# LAB03-1_2020-11-16_17-36-06.net
KiCad netlist of a schematic drawn in EasyEDA
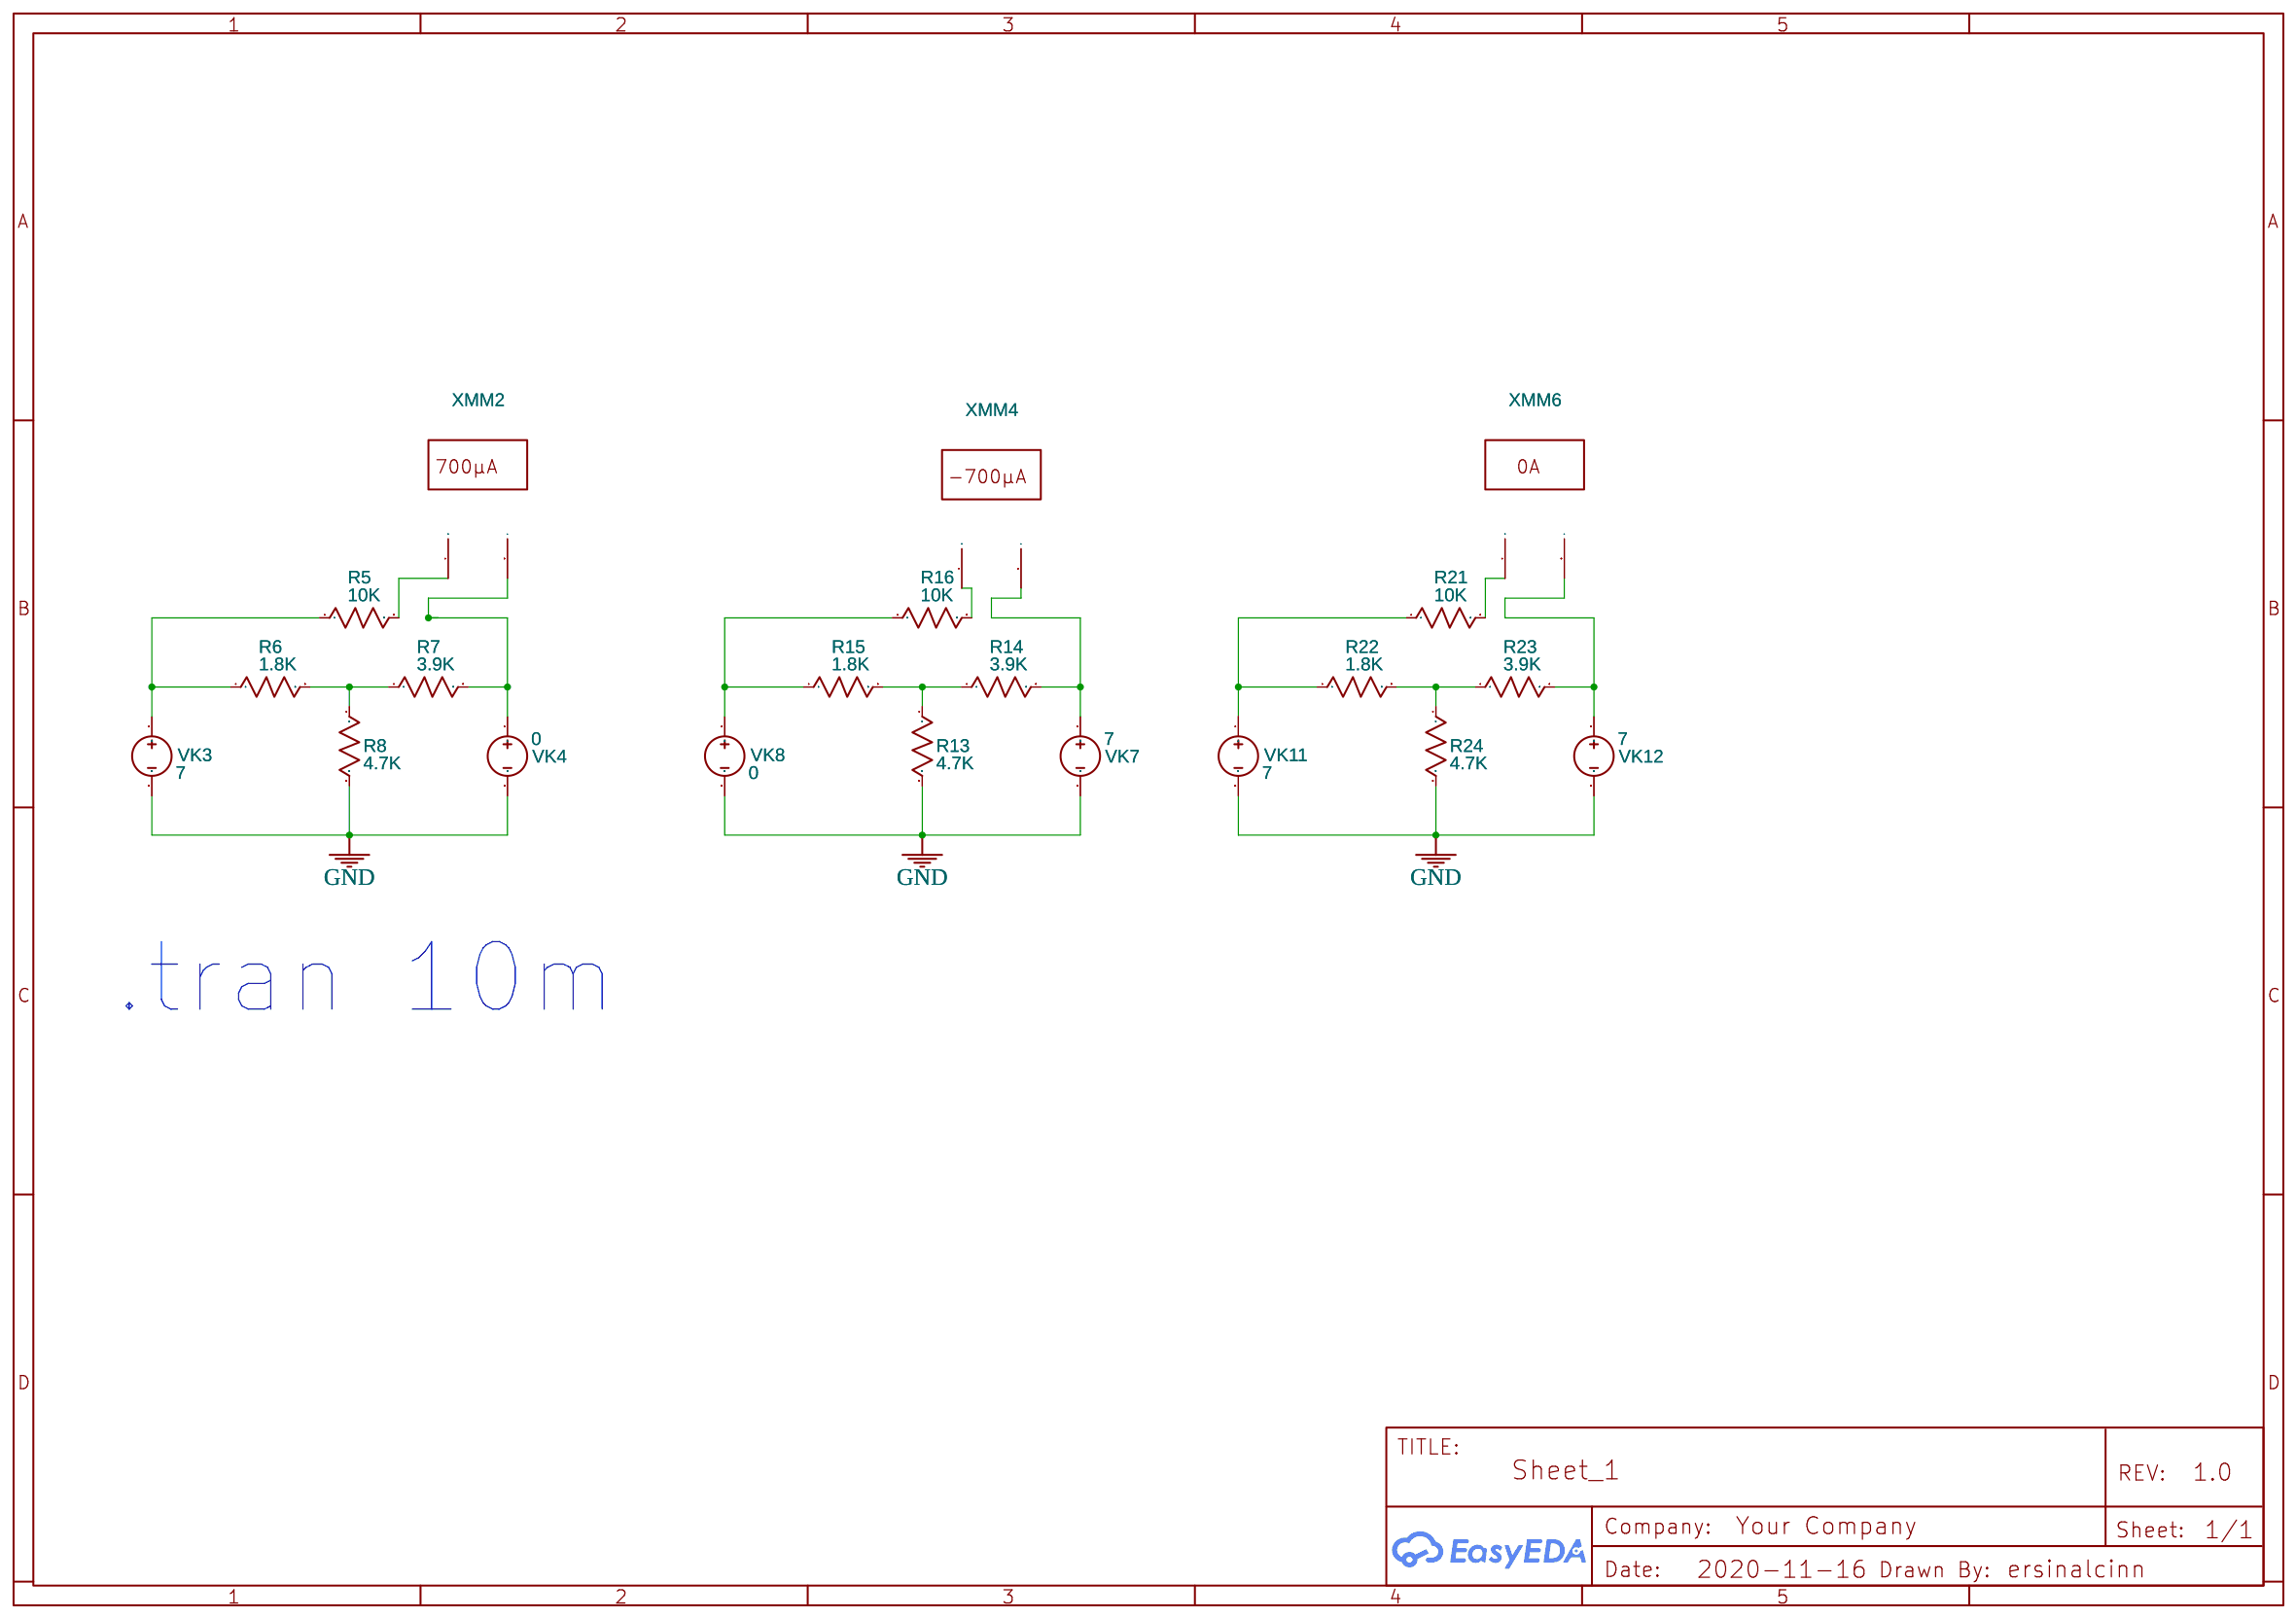
[diagram p0: schematic sheet]

(export (version "E")
  (design (tool "Eeschema 10.0.6"))
  (components
    (comp (ref "R5") (value "10K") (libsource (lib "") (part "Resistor_US")))
    (comp (ref "R6") (value "1.8K") (libsource (lib "") (part "Resistor_US")))
    (comp (ref "R7") (value "3.9K") (libsource (lib "") (part "Resistor_US")))
    (comp (ref "R8") (value "4.7K") (libsource (lib "") (part "Resistor_US_1")))
    (comp (ref "R13") (value "4.7K") (libsource (lib "") (part "Resistor_US_1")))
    (comp (ref "R14") (value "3.9K") (libsource (lib "") (part "Resistor_US")))
    (comp (ref "R15") (value "1.8K") (libsource (lib "") (part "Resistor_US")))
    (comp (ref "R16") (value "10K") (libsource (lib "") (part "Resistor_US")))
    (comp (ref "R21") (value "10K") (libsource (lib "") (part "Resistor_US")))
    (comp (ref "R22") (value "1.8K") (libsource (lib "") (part "Resistor_US")))
    (comp (ref "R23") (value "3.9K") (libsource (lib "") (part "Resistor_US")))
    (comp (ref "R24") (value "4.7K") (libsource (lib "") (part "Resistor_US_1")))
    (comp (ref "VK3") (value "7") (libsource (lib "") (part "VDC")))
    (comp (ref "VK4") (value "0") (libsource (lib "") (part "VDC_1")))
    (comp (ref "VK7") (value "7") (libsource (lib "") (part "VDC_1")))
    (comp (ref "VK8") (value "0") (libsource (lib "") (part "VDC")))
    (comp (ref "VK11") (value "7") (libsource (lib "") (part "VDC")))
    (comp (ref "VK12") (value "7") (libsource (lib "") (part "VDC_1")))
    (comp (ref "XMM2") (value "Multimeter") (libsource (lib "") (part "MULTIMETER_2")))
    (comp (ref "XMM4") (value "Multimeter") (libsource (lib "") (part "MULTIMETER")))
    (comp (ref "XMM6") (value "Multimeter") (libsource (lib "") (part "MULTIMETER_1")))
  )
  (nets
    (net (code "1") (name "GND") (class "Default")
      (node (ref "R13") (pin "2") (pinfunction "2_2") (pintype "unspecified"))
      (node (ref "R24") (pin "2") (pinfunction "2_2") (pintype "unspecified"))
      (node (ref "R8") (pin "2") (pinfunction "2_2") (pintype "unspecified"))
      (node (ref "VK11") (pin "2") (pinfunction "2_2") (pintype "unspecified"))
      (node (ref "VK12") (pin "2") (pinfunction "2_2") (pintype "unspecified"))
      (node (ref "VK3") (pin "2") (pinfunction "2_2") (pintype "unspecified"))
      (node (ref "VK4") (pin "2") (pinfunction "2_2") (pintype "unspecified"))
      (node (ref "VK7") (pin "2") (pinfunction "2_2") (pintype "unspecified"))
      (node (ref "VK8") (pin "2") (pinfunction "2_2") (pintype "unspecified"))
    )
    (net (code "2") (name "Net-(R5-Pad1)") (class "Default")
      (node (ref "R5") (pin "1") (pinfunction "1_1") (pintype "unspecified"))
      (node (ref "R6") (pin "1") (pinfunction "1_1") (pintype "unspecified"))
      (node (ref "VK3") (pin "1") (pinfunction "1_1") (pintype "unspecified"))
    )
    (net (code "3") (name "Net-(R6-Pad2)") (class "Default")
      (node (ref "R6") (pin "2") (pinfunction "2_2") (pintype "unspecified"))
      (node (ref "R7") (pin "1") (pinfunction "1_1") (pintype "unspecified"))
      (node (ref "R8") (pin "1") (pinfunction "1_1") (pintype "unspecified"))
    )
    (net (code "4") (name "Net-(R13-Pad1)") (class "Default")
      (node (ref "R13") (pin "1") (pinfunction "1_1") (pintype "unspecified"))
      (node (ref "R14") (pin "1") (pinfunction "1_1") (pintype "unspecified"))
      (node (ref "R15") (pin "2") (pinfunction "2_2") (pintype "unspecified"))
    )
    (net (code "5") (name "Net-(R15-Pad1)") (class "Default")
      (node (ref "R15") (pin "1") (pinfunction "1_1") (pintype "unspecified"))
      (node (ref "R16") (pin "1") (pinfunction "1_1") (pintype "unspecified"))
      (node (ref "VK8") (pin "1") (pinfunction "1_1") (pintype "unspecified"))
    )
    (net (code "6") (name "Net-(R21-Pad1)") (class "Default")
      (node (ref "R21") (pin "1") (pinfunction "1_1") (pintype "unspecified"))
      (node (ref "R22") (pin "1") (pinfunction "1_1") (pintype "unspecified"))
      (node (ref "VK11") (pin "1") (pinfunction "1_1") (pintype "unspecified"))
    )
    (net (code "7") (name "Net-(R22-Pad2)") (class "Default")
      (node (ref "R22") (pin "2") (pinfunction "2_2") (pintype "unspecified"))
      (node (ref "R23") (pin "1") (pinfunction "1_1") (pintype "unspecified"))
      (node (ref "R24") (pin "1") (pinfunction "1_1") (pintype "unspecified"))
    )
    (net (code "8") (name "Net-(XMM2-+)") (class "Default")
      (node (ref "R5") (pin "2") (pinfunction "2_2") (pintype "unspecified"))
      (node (ref "XMM2") (pin "1") (pinfunction "+_1") (pintype "unspecified"))
    )
    (net (code "9") (name "Net-(XMM2-I)") (class "Default")
      (node (ref "R7") (pin "2") (pinfunction "2_2") (pintype "unspecified"))
      (node (ref "VK4") (pin "1") (pinfunction "1_1") (pintype "unspecified"))
      (node (ref "XMM2") (pin "2") (pinfunction "I_2") (pintype "unspecified"))
    )
    (net (code "10") (name "Net-(XMM4-+)") (class "Default")
      (node (ref "R16") (pin "2") (pinfunction "2_2") (pintype "unspecified"))
      (node (ref "XMM4") (pin "1") (pinfunction "+_1") (pintype "unspecified"))
    )
    (net (code "11") (name "Net-(XMM4-I)") (class "Default")
      (node (ref "R14") (pin "2") (pinfunction "2_2") (pintype "unspecified"))
      (node (ref "VK7") (pin "1") (pinfunction "1_1") (pintype "unspecified"))
      (node (ref "XMM4") (pin "2") (pinfunction "I_2") (pintype "unspecified"))
    )
    (net (code "12") (name "Net-(XMM6-+)") (class "Default")
      (node (ref "R21") (pin "2") (pinfunction "2_2") (pintype "unspecified"))
      (node (ref "XMM6") (pin "1") (pinfunction "+_1") (pintype "unspecified"))
    )
    (net (code "13") (name "Net-(XMM6-I)") (class "Default")
      (node (ref "R23") (pin "2") (pinfunction "2_2") (pintype "unspecified"))
      (node (ref "VK12") (pin "1") (pinfunction "1_1") (pintype "unspecified"))
      (node (ref "XMM6") (pin "2") (pinfunction "I_2") (pintype "unspecified"))
    )
  )
)
